# Relay_Bypass_v1_1.net
KiCad netlist of a schematic drawn in EAGLE
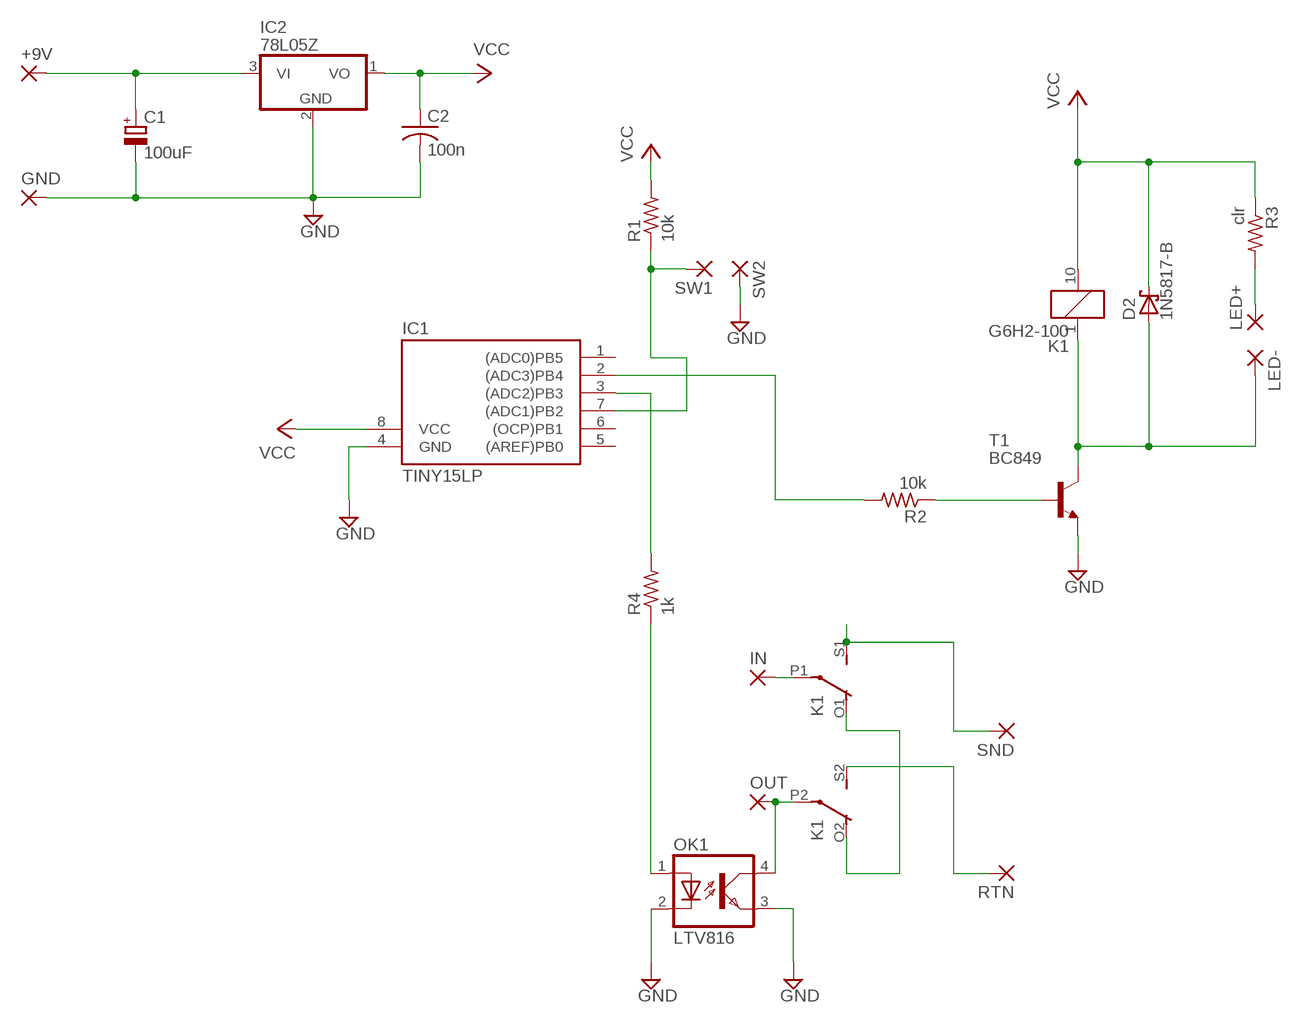
[diagram p0: schematic, sheet 1]

(export (version "E")
  (design (tool "Eeschema 10.0.6"))
  (components
    (comp (ref "+9V")
      (value "2,54/0,9")
      (footprint "eagle-import:2,54_0,9")
      (libsource (lib "eagle-import") (part "2,54/0,9"))
    )
    (comp (ref "C1")
      (value "100uF")
      (footprint "eagle-import:E2,5-5")
      (libsource (lib "eagle-import") (part "CPOL-EUE2.5-5"))
    )
    (comp (ref "C2")
      (value "100n")
      (footprint "eagle-import:C050-025X075")
      (libsource (lib "eagle-import") (part "C-US050-025X075"))
    )
    (comp (ref "D2")
      (value "1N5817-B")
      (footprint "eagle-import:DO41-7.6")
      (libsource (lib "eagle-import") (part "1N5817-B"))
    )
    (comp (ref "GND")
      (value "2,54/0,9")
      (footprint "eagle-import:2,54_0,9")
      (libsource (lib "eagle-import") (part "2,54/0,9"))
    )
    (comp (ref "IC1")
      (value "TINY15LP")
      (footprint "eagle-import:DIL08")
      (libsource (lib "eagle-import") (part "TINY15LP"))
    )
    (comp (ref "IC2")
      (value "78L05Z")
      (footprint "eagle-import:TO92")
      (libsource (lib "eagle-import") (part "78ZL05"))
    )
    (comp (ref "IN")
      (value "2,54/0,9")
      (footprint "eagle-import:2,54_0,9")
      (libsource (lib "eagle-import") (part "2,54/0,9"))
    )
    (comp (ref "K1")
      (value "G6H2-100")
      (footprint "eagle-import:G6H2-100")
      (libsource (lib "eagle-import") (part "G6H2-100"))
    )
    (comp (ref "LED+")
      (value "2,54/0,9")
      (footprint "eagle-import:2,54_0,9")
      (libsource (lib "eagle-import") (part "2,54/0,9"))
    )
    (comp (ref "LED-")
      (value "2,54/0,9")
      (footprint "eagle-import:2,54_0,9")
      (libsource (lib "eagle-import") (part "2,54/0,9"))
    )
    (comp (ref "OK1")
      (value "LTV816")
      (footprint "eagle-import:DIL04")
      (libsource (lib "eagle-import") (part "LTV816"))
    )
    (comp (ref "OUT")
      (value "2,54/0,9")
      (footprint "eagle-import:2,54_0,9")
      (libsource (lib "eagle-import") (part "2,54/0,9"))
    )
    (comp (ref "R1")
      (value "10k")
      (footprint "eagle-import:R0805")
      (libsource (lib "eagle-import") (part "R-US_R0805"))
    )
    (comp (ref "R2")
      (value "10k")
      (footprint "eagle-import:R0805")
      (libsource (lib "eagle-import") (part "R-US_R0805"))
    )
    (comp (ref "R3")
      (value "clr")
      (footprint "eagle-import:R0805")
      (libsource (lib "eagle-import") (part "R-US_R0805"))
    )
    (comp (ref "R4")
      (value "1k")
      (footprint "eagle-import:R0805")
      (libsource (lib "eagle-import") (part "R-US_R0805"))
    )
    (comp (ref "RTN")
      (value "2,54/0,9")
      (footprint "eagle-import:2,54_0,9")
      (libsource (lib "eagle-import") (part "2,54/0,9"))
    )
    (comp (ref "SND")
      (value "2,54/0,9")
      (footprint "eagle-import:2,54_0,9")
      (libsource (lib "eagle-import") (part "2,54/0,9"))
    )
    (comp (ref "SW1")
      (value "2,54/0,9")
      (footprint "eagle-import:2,54_0,9")
      (libsource (lib "eagle-import") (part "2,54/0,9"))
    )
    (comp (ref "SW2")
      (value "2,54/0,9")
      (footprint "eagle-import:2,54_0,9")
      (libsource (lib "eagle-import") (part "2,54/0,9"))
    )
    (comp (ref "T1")
      (value "BC849")
      (footprint "eagle-import:SOT23")
      (libsource (lib "eagle-import") (part "BC849"))
    )
  )
  (nets
    (net (code "1") (name "GND") (class "Default")
      (node (ref "C1") (pin "-") (pinfunction "-_-") (pintype "passive"))
      (node (ref "C2") (pin "2") (pinfunction "2_2") (pintype "passive"))
      (node (ref "GND") (pin "1") (pinfunction "P_1") (pintype "passive"))
      (node (ref "IC1") (pin "4") (pinfunction "GND_4") (pintype "power_in"))
      (node (ref "IC2") (pin "2") (pinfunction "GND_2") (pintype "passive"))
      (node (ref "OK1") (pin "2") (pinfunction "C_2") (pintype "passive"))
      (node (ref "OK1") (pin "3") (pinfunction "EMIT_3") (pintype "passive"))
      (node (ref "SW2") (pin "1") (pinfunction "P_1") (pintype "passive"))
      (node (ref "T1") (pin "2") (pinfunction "E_2") (pintype "passive"))
    )
    (net (code "2") (name "Net-(+9V-P)") (class "Default")
      (node (ref "+9V") (pin "1") (pinfunction "P_1") (pintype "passive"))
      (node (ref "C1") (pin "+") (pinfunction "+_+") (pintype "passive"))
      (node (ref "IC2") (pin "3") (pinfunction "VI_3") (pintype "input"))
    )
    (net (code "3") (name "Net-(IC1-(ADC1)PB2)") (class "Default")
      (node (ref "IC1") (pin "7") (pinfunction "(ADC1)PB2_7") (pintype "bidirectional"))
      (node (ref "R1") (pin "1") (pinfunction "1_1") (pintype "passive"))
      (node (ref "SW1") (pin "1") (pinfunction "P_1") (pintype "passive"))
    )
    (net (code "4") (name "Net-(IC1-(ADC2)PB3)") (class "Default")
      (node (ref "IC1") (pin "3") (pinfunction "(ADC2)PB3_3") (pintype "bidirectional"))
      (node (ref "R4") (pin "2") (pinfunction "2_2") (pintype "passive"))
    )
    (net (code "5") (name "Net-(IC1-(ADC3)PB4)") (class "Default")
      (node (ref "IC1") (pin "2") (pinfunction "(ADC3)PB4_2") (pintype "bidirectional"))
      (node (ref "R2") (pin "2") (pinfunction "2_2") (pintype "passive"))
    )
    (net (code "6") (name "Net-(IN-P)") (class "Default")
      (node (ref "IN") (pin "1") (pinfunction "P_1") (pintype "passive"))
      (node (ref "K1") (pin "P1") (pinfunction "P_P1") (pintype "passive"))
    )
    (net (code "7") (name "Net-(K1B-O)") (class "Default")
      (node (ref "K1") (pin "O1") (pinfunction "O_O1") (pintype "passive"))
      (node (ref "K1") (pin "O2") (pinfunction "O_O2") (pintype "passive"))
    )
    (net (code "8") (name "Net-(K1B-S)") (class "Default")
      (node (ref "K1") (pin "S1") (pinfunction "S_S1") (pintype "passive"))
      (node (ref "SND") (pin "1") (pinfunction "P_1") (pintype "passive"))
    )
    (net (code "9") (name "Net-(K1C-P)") (class "Default")
      (node (ref "K1") (pin "P2") (pinfunction "P_P2") (pintype "passive"))
      (node (ref "OK1") (pin "4") (pinfunction "COL_4") (pintype "passive"))
      (node (ref "OUT") (pin "1") (pinfunction "P_1") (pintype "passive"))
    )
    (net (code "10") (name "Net-(K1C-S)") (class "Default")
      (node (ref "K1") (pin "S2") (pinfunction "S_S2") (pintype "passive"))
      (node (ref "RTN") (pin "1") (pinfunction "P_1") (pintype "passive"))
    )
    (net (code "11") (name "Net-(LED+-P)") (class "Default")
      (node (ref "LED+") (pin "1") (pinfunction "P_1") (pintype "passive"))
      (node (ref "R3") (pin "2") (pinfunction "2_2") (pintype "passive"))
    )
    (net (code "12") (name "Net-(LED--P)") (class "Default")
      (node (ref "D2") (pin "A") (pinfunction "A_A") (pintype "passive"))
      (node (ref "K1") (pin "1") (pinfunction "1_1") (pintype "passive"))
      (node (ref "LED-") (pin "1") (pinfunction "P_1") (pintype "passive"))
      (node (ref "T1") (pin "3") (pinfunction "C_3") (pintype "passive"))
    )
    (net (code "13") (name "Net-(OK1-A)") (class "Default")
      (node (ref "OK1") (pin "1") (pinfunction "A_1") (pintype "passive"))
      (node (ref "R4") (pin "1") (pinfunction "1_1") (pintype "passive"))
    )
    (net (code "14") (name "Net-(T1-B)") (class "Default")
      (node (ref "R2") (pin "1") (pinfunction "1_1") (pintype "passive"))
      (node (ref "T1") (pin "1") (pinfunction "B_1") (pintype "passive"))
    )
    (net (code "15") (name "VCC") (class "Default")
      (node (ref "C2") (pin "1") (pinfunction "1_1") (pintype "passive"))
      (node (ref "D2") (pin "C") (pinfunction "C_C") (pintype "passive"))
      (node (ref "IC1") (pin "8") (pinfunction "VCC_8") (pintype "power_in"))
      (node (ref "IC2") (pin "1") (pinfunction "VO_1") (pintype "passive"))
      (node (ref "K1") (pin "10") (pinfunction "2_10") (pintype "passive"))
      (node (ref "R1") (pin "2") (pinfunction "2_2") (pintype "passive"))
      (node (ref "R3") (pin "1") (pinfunction "1_1") (pintype "passive"))
    )
    (net (code "16") (name "unconnected-(IC1-(ADC0)PB5-Pad1)") (class "Default")
      (node (ref "IC1") (pin "1") (pinfunction "(ADC0)PB5_1") (pintype "bidirectional"))
    )
    (net (code "17") (name "unconnected-(IC1-(AREF)PB0-Pad5)") (class "Default")
      (node (ref "IC1") (pin "5") (pinfunction "(AREF)PB0_5") (pintype "bidirectional"))
    )
    (net (code "18") (name "unconnected-(IC1-(OCP)PB1-Pad6)") (class "Default")
      (node (ref "IC1") (pin "6") (pinfunction "(OCP)PB1_6") (pintype "bidirectional"))
    )
  )
)
